# kilo-issue2.net
KiCad netlist of a schematic drawn in EAGLE
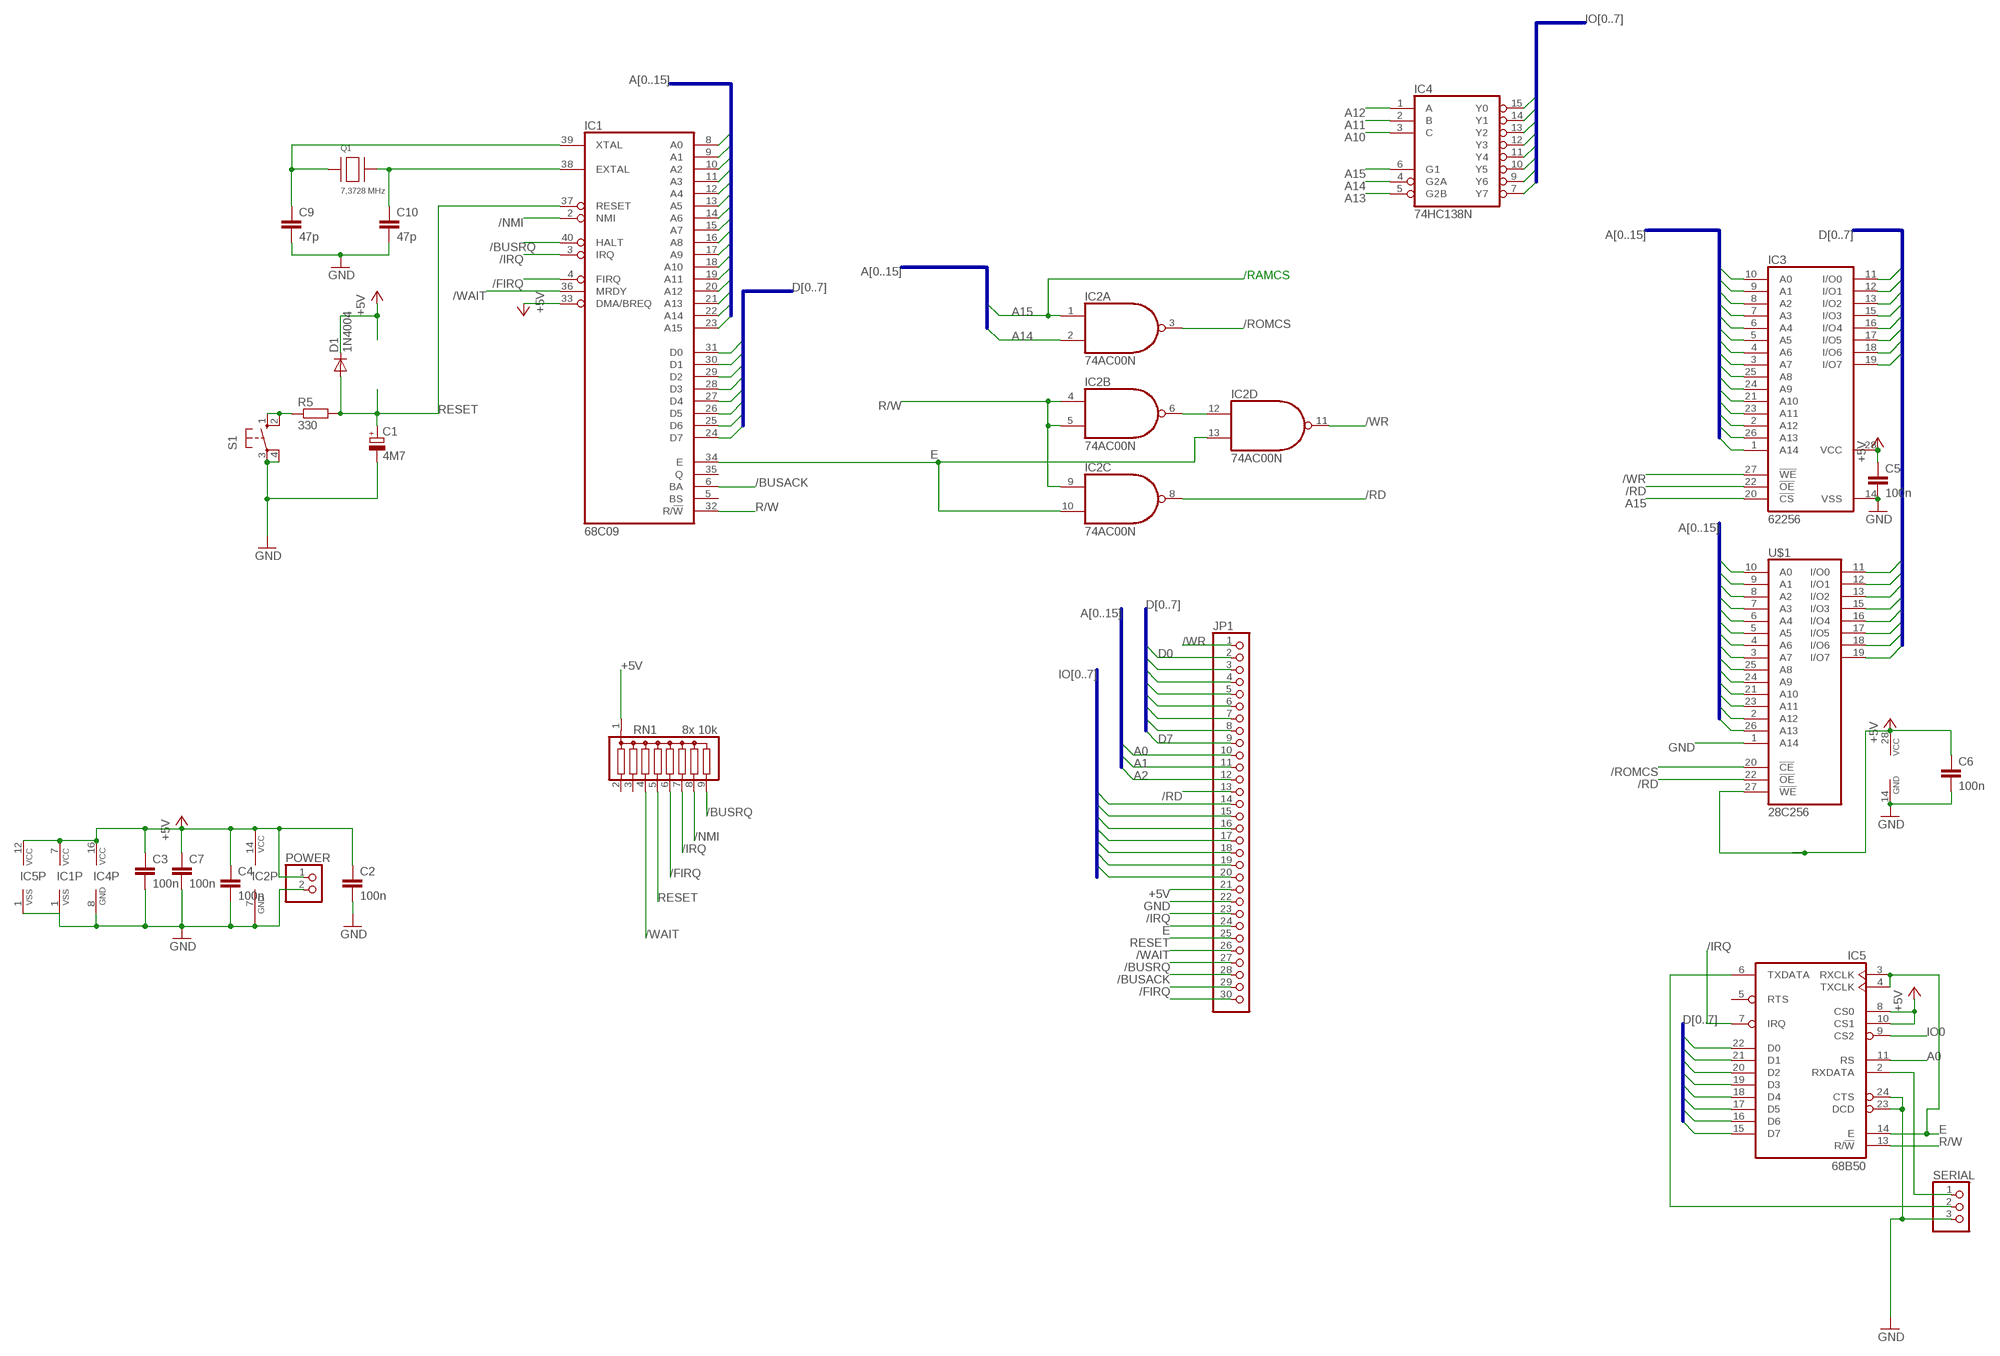
[diagram p0: schematic, sheet 1]

(export (version "E")
  (design (tool "Eeschema 10.0.6"))
  (components
    (comp (ref "C1")
      (value "4M7")
      (footprint "eagle-import:E2,5-6")
      (libsource (lib "eagle-import") (part "CPOL-EUE2.5-6"))
    )
    (comp (ref "C2")
      (value "100n")
      (footprint "eagle-import:C025-030X050")
      (libsource (lib "eagle-import") (part "C-EU025-030X050"))
    )
    (comp (ref "C3")
      (value "100n")
      (footprint "eagle-import:C025-030X050")
      (libsource (lib "eagle-import") (part "C-EU025-030X050"))
    )
    (comp (ref "C4")
      (value "100n")
      (footprint "eagle-import:C025-030X050")
      (libsource (lib "eagle-import") (part "C-EU025-030X050"))
    )
    (comp (ref "C5")
      (value "100n")
      (footprint "eagle-import:C025-030X050")
      (libsource (lib "eagle-import") (part "C-EU025-030X050"))
    )
    (comp (ref "C6")
      (value "100n")
      (footprint "eagle-import:C025-030X050")
      (libsource (lib "eagle-import") (part "C-EU025-030X050"))
    )
    (comp (ref "C7")
      (value "100n")
      (footprint "eagle-import:C025-030X050")
      (libsource (lib "eagle-import") (part "C-EU025-030X050"))
    )
    (comp (ref "C9")
      (value "47p")
      (footprint "eagle-import:C025-030X050")
      (libsource (lib "eagle-import") (part "C-EU025-030X050"))
    )
    (comp (ref "C10")
      (value "47p")
      (footprint "eagle-import:C025-030X050")
      (libsource (lib "eagle-import") (part "C-EU025-030X050"))
    )
    (comp (ref "D1")
      (value "1N4004")
      (footprint "eagle-import:DO41-10")
      (libsource (lib "eagle-import") (part "1N4004"))
    )
    (comp (ref "IC1")
      (value "68C09")
      (footprint "eagle-import:DIL40")
      (fields (field (name "MF") "NTE ELECTRONICS") (field (name "MPN") "NTE6809"))
      (libsource (lib "eagle-import") (part "6809"))
    )
    (comp (ref "IC2")
      (value "74AC00N")
      (footprint "eagle-import:DIL14")
      (libsource (lib "eagle-import") (part "7400NALS"))
    )
    (comp (ref "IC3")
      (value "62256")
      (footprint "eagle-import:DIL28-6")
      (libsource (lib "eagle-import") (part "62256P"))
    )
    (comp (ref "IC4")
      (value "74HC138N")
      (footprint "eagle-import:DIL16")
      (libsource (lib "eagle-import") (part "74138NHC"))
    )
    (comp (ref "IC5")
      (value "68B50")
      (footprint "eagle-import:DIL24")
      (fields (field (name "MF") "NTE ELECTRONICS") (field (name "MPN") "NTE6850"))
      (libsource (lib "eagle-import") (part "6850"))
    )
    (comp (ref "JP1")
      (value "PINHD-1X30")
      (footprint "eagle-import:1X30")
      (libsource (lib "eagle-import") (part "PINHD-1X30"))
    )
    (comp (ref "POWER")
      (value "PINHD-1X2")
      (footprint "eagle-import:1X02")
      (libsource (lib "eagle-import") (part "PINHD-1X2"))
    )
    (comp (ref "Q1")
      (value "7,3728 MHz")
      (footprint "eagle-import:HC49US")
      (libsource (lib "eagle-import") (part "306010080_XTAL_8MHZ_HC49US"))
    )
    (comp (ref "R5")
      (value "330")
      (footprint "eagle-import:0207_7")
      (libsource (lib "eagle-import") (part "R-EU_0207/7"))
    )
    (comp (ref "RN1")
      (value "8x 10k")
      (footprint "eagle-import:SIL9")
      (libsource (lib "eagle-import") (part "G08R"))
    )
    (comp (ref "S1")
      (value "40-XX")
      (footprint "eagle-import:B3F-40XX")
      (fields (field (name "MF") "OMRON COMPONENTS USA") (field (name "MPN") "B3F-4000"))
      (libsource (lib "eagle-import") (part "40-XX"))
    )
    (comp (ref "SERIAL")
      (value "PINHD-1X3")
      (footprint "eagle-import:1X03")
      (libsource (lib "eagle-import") (part "PINHD-1X3"))
    )
    (comp (ref "U$1")
      (value "28C256")
      (footprint "eagle-import:DIL28")
      (libsource (lib "eagle-import") (part "28C256"))
    )
  )
  (nets
    (net (code "1") (name "+5V") (class "Default")
      (node (ref "C2") (pin "1") (pinfunction "1_1") (pintype "passive"))
      (node (ref "C3") (pin "1") (pinfunction "1_1") (pintype "passive"))
      (node (ref "C4") (pin "1") (pinfunction "1_1") (pintype "passive"))
      (node (ref "C5") (pin "1") (pinfunction "1_1") (pintype "passive"))
      (node (ref "C6") (pin "1") (pinfunction "1_1") (pintype "passive"))
      (node (ref "C7") (pin "1") (pinfunction "1_1") (pintype "passive"))
      (node (ref "D1") (pin "C") (pinfunction "C_C") (pintype "passive"))
      (node (ref "IC1") (pin "33") (pinfunction "DMA/BREQ_33") (pintype "input"))
      (node (ref "IC1") (pin "7") (pinfunction "VCC_7") (pintype "power_in"))
      (node (ref "IC2") (pin "14") (pinfunction "VCC_14") (pintype "power_in"))
      (node (ref "IC3") (pin "28") (pinfunction "VCC_28") (pintype "power_in"))
      (node (ref "IC4") (pin "16") (pinfunction "VCC_16") (pintype "power_in"))
      (node (ref "IC5") (pin "10") (pinfunction "CS1_10") (pintype "input"))
      (node (ref "IC5") (pin "12") (pinfunction "VCC_12") (pintype "power_in"))
      (node (ref "IC5") (pin "8") (pinfunction "CS0_8") (pintype "input"))
      (node (ref "JP1") (pin "21") (pinfunction "21_21") (pintype "passive"))
      (node (ref "POWER") (pin "1") (pinfunction "1_1") (pintype "passive"))
      (node (ref "RN1") (pin "1") (pinfunction "1_1") (pintype "passive"))
      (node (ref "U$1") (pin "27") (pinfunction "~{WE}_27") (pintype "input"))
      (node (ref "U$1") (pin "28") (pinfunction "VCC_28") (pintype "power_in"))
    )
    (net (code "5") (name "A0") (class "Default")
      (node (ref "IC1") (pin "8") (pinfunction "A0_8") (pintype "tri_state"))
      (node (ref "IC3") (pin "10") (pinfunction "A0_10") (pintype "input"))
      (node (ref "IC5") (pin "11") (pinfunction "RS_11") (pintype "input"))
      (node (ref "JP1") (pin "10") (pinfunction "10_10") (pintype "passive"))
      (node (ref "U$1") (pin "10") (pinfunction "A0_10") (pintype "input"))
    )
    (net (code "6") (name "A1") (class "Default")
      (node (ref "IC1") (pin "9") (pinfunction "A1_9") (pintype "tri_state"))
      (node (ref "IC3") (pin "9") (pinfunction "A1_9") (pintype "input"))
      (node (ref "JP1") (pin "11") (pinfunction "11_11") (pintype "passive"))
      (node (ref "U$1") (pin "9") (pinfunction "A1_9") (pintype "input"))
    )
    (net (code "7") (name "A2") (class "Default")
      (node (ref "IC1") (pin "10") (pinfunction "A2_10") (pintype "tri_state"))
      (node (ref "IC3") (pin "8") (pinfunction "A2_8") (pintype "input"))
      (node (ref "JP1") (pin "12") (pinfunction "12_12") (pintype "passive"))
      (node (ref "U$1") (pin "8") (pinfunction "A2_8") (pintype "input"))
    )
    (net (code "8") (name "A3") (class "Default")
      (node (ref "IC1") (pin "11") (pinfunction "A3_11") (pintype "tri_state"))
      (node (ref "IC3") (pin "7") (pinfunction "A3_7") (pintype "input"))
      (node (ref "U$1") (pin "7") (pinfunction "A3_7") (pintype "input"))
    )
    (net (code "9") (name "A4") (class "Default")
      (node (ref "IC1") (pin "12") (pinfunction "A4_12") (pintype "tri_state"))
      (node (ref "IC3") (pin "6") (pinfunction "A4_6") (pintype "input"))
      (node (ref "U$1") (pin "6") (pinfunction "A4_6") (pintype "input"))
    )
    (net (code "10") (name "A5") (class "Default")
      (node (ref "IC1") (pin "13") (pinfunction "A5_13") (pintype "tri_state"))
      (node (ref "IC3") (pin "5") (pinfunction "A5_5") (pintype "input"))
      (node (ref "U$1") (pin "5") (pinfunction "A5_5") (pintype "input"))
    )
    (net (code "11") (name "A6") (class "Default")
      (node (ref "IC1") (pin "14") (pinfunction "A6_14") (pintype "tri_state"))
      (node (ref "IC3") (pin "4") (pinfunction "A6_4") (pintype "input"))
      (node (ref "U$1") (pin "4") (pinfunction "A6_4") (pintype "input"))
    )
    (net (code "12") (name "A7") (class "Default")
      (node (ref "IC1") (pin "15") (pinfunction "A7_15") (pintype "tri_state"))
      (node (ref "IC3") (pin "3") (pinfunction "A7_3") (pintype "input"))
      (node (ref "U$1") (pin "3") (pinfunction "A7_3") (pintype "input"))
    )
    (net (code "13") (name "A8") (class "Default")
      (node (ref "IC1") (pin "16") (pinfunction "A8_16") (pintype "tri_state"))
      (node (ref "IC3") (pin "25") (pinfunction "A8_25") (pintype "input"))
      (node (ref "U$1") (pin "25") (pinfunction "A8_25") (pintype "input"))
    )
    (net (code "14") (name "A9") (class "Default")
      (node (ref "IC1") (pin "17") (pinfunction "A9_17") (pintype "tri_state"))
      (node (ref "IC3") (pin "24") (pinfunction "A9_24") (pintype "input"))
      (node (ref "U$1") (pin "24") (pinfunction "A9_24") (pintype "input"))
    )
    (net (code "15") (name "A10") (class "Default")
      (node (ref "IC1") (pin "18") (pinfunction "A10_18") (pintype "tri_state"))
      (node (ref "IC3") (pin "21") (pinfunction "A10_21") (pintype "input"))
      (node (ref "IC4") (pin "3") (pinfunction "C_3") (pintype "input"))
      (node (ref "U$1") (pin "21") (pinfunction "A10_21") (pintype "input"))
    )
    (net (code "16") (name "A11") (class "Default")
      (node (ref "IC1") (pin "19") (pinfunction "A11_19") (pintype "tri_state"))
      (node (ref "IC3") (pin "23") (pinfunction "A11_23") (pintype "input"))
      (node (ref "IC4") (pin "2") (pinfunction "B_2") (pintype "input"))
      (node (ref "U$1") (pin "23") (pinfunction "A11_23") (pintype "input"))
    )
    (net (code "17") (name "A12") (class "Default")
      (node (ref "IC1") (pin "20") (pinfunction "A12_20") (pintype "tri_state"))
      (node (ref "IC3") (pin "2") (pinfunction "A12_2") (pintype "input"))
      (node (ref "IC4") (pin "1") (pinfunction "A_1") (pintype "input"))
      (node (ref "U$1") (pin "2") (pinfunction "A12_2") (pintype "input"))
    )
    (net (code "18") (name "A13") (class "Default")
      (node (ref "IC1") (pin "21") (pinfunction "A13_21") (pintype "tri_state"))
      (node (ref "IC3") (pin "26") (pinfunction "A13_26") (pintype "input"))
      (node (ref "IC4") (pin "5") (pinfunction "G2B_5") (pintype "input"))
      (node (ref "U$1") (pin "26") (pinfunction "A13_26") (pintype "input"))
    )
    (net (code "19") (name "A14") (class "Default")
      (node (ref "IC1") (pin "22") (pinfunction "A14_22") (pintype "tri_state"))
      (node (ref "IC2") (pin "2") (pinfunction "I1_2") (pintype "input"))
      (node (ref "IC3") (pin "1") (pinfunction "A14_1") (pintype "input"))
      (node (ref "IC4") (pin "4") (pinfunction "G2A_4") (pintype "input"))
    )
    (net (code "20") (name "A15") (class "Default")
      (node (ref "IC1") (pin "23") (pinfunction "A15_23") (pintype "tri_state"))
      (node (ref "IC2") (pin "1") (pinfunction "I0_1") (pintype "input"))
      (node (ref "IC3") (pin "20") (pinfunction "~{CS}_20") (pintype "input"))
      (node (ref "IC4") (pin "6") (pinfunction "G1_6") (pintype "input"))
    )
    (net (code "21") (name "D0") (class "Default")
      (node (ref "IC1") (pin "31") (pinfunction "D0_31") (pintype "bidirectional"))
      (node (ref "IC3") (pin "11") (pinfunction "I/O0_11") (pintype "bidirectional"))
      (node (ref "IC5") (pin "22") (pinfunction "D0_22") (pintype "bidirectional"))
      (node (ref "JP1") (pin "2") (pinfunction "2_2") (pintype "passive"))
      (node (ref "U$1") (pin "11") (pinfunction "I/O0_11") (pintype "tri_state"))
    )
    (net (code "22") (name "D1") (class "Default")
      (node (ref "IC1") (pin "30") (pinfunction "D1_30") (pintype "bidirectional"))
      (node (ref "IC3") (pin "12") (pinfunction "I/O1_12") (pintype "bidirectional"))
      (node (ref "IC5") (pin "21") (pinfunction "D1_21") (pintype "bidirectional"))
      (node (ref "JP1") (pin "3") (pinfunction "3_3") (pintype "passive"))
      (node (ref "U$1") (pin "12") (pinfunction "I/O1_12") (pintype "tri_state"))
    )
    (net (code "23") (name "D2") (class "Default")
      (node (ref "IC1") (pin "29") (pinfunction "D2_29") (pintype "bidirectional"))
      (node (ref "IC3") (pin "13") (pinfunction "I/O2_13") (pintype "bidirectional"))
      (node (ref "IC5") (pin "20") (pinfunction "D2_20") (pintype "bidirectional"))
      (node (ref "JP1") (pin "4") (pinfunction "4_4") (pintype "passive"))
      (node (ref "U$1") (pin "13") (pinfunction "I/O2_13") (pintype "tri_state"))
    )
    (net (code "24") (name "D3") (class "Default")
      (node (ref "IC1") (pin "28") (pinfunction "D3_28") (pintype "bidirectional"))
      (node (ref "IC3") (pin "15") (pinfunction "I/O3_15") (pintype "bidirectional"))
      (node (ref "IC5") (pin "19") (pinfunction "D3_19") (pintype "bidirectional"))
      (node (ref "JP1") (pin "5") (pinfunction "5_5") (pintype "passive"))
      (node (ref "U$1") (pin "15") (pinfunction "I/O3_15") (pintype "tri_state"))
    )
    (net (code "25") (name "D4") (class "Default")
      (node (ref "IC1") (pin "27") (pinfunction "D4_27") (pintype "bidirectional"))
      (node (ref "IC3") (pin "16") (pinfunction "I/O4_16") (pintype "bidirectional"))
      (node (ref "IC5") (pin "18") (pinfunction "D4_18") (pintype "bidirectional"))
      (node (ref "JP1") (pin "6") (pinfunction "6_6") (pintype "passive"))
      (node (ref "U$1") (pin "16") (pinfunction "I/O4_16") (pintype "tri_state"))
    )
    (net (code "26") (name "D5") (class "Default")
      (node (ref "IC1") (pin "26") (pinfunction "D5_26") (pintype "bidirectional"))
      (node (ref "IC3") (pin "17") (pinfunction "I/O5_17") (pintype "bidirectional"))
      (node (ref "IC5") (pin "17") (pinfunction "D5_17") (pintype "bidirectional"))
      (node (ref "JP1") (pin "7") (pinfunction "7_7") (pintype "passive"))
      (node (ref "U$1") (pin "17") (pinfunction "I/O5_17") (pintype "tri_state"))
    )
    (net (code "27") (name "D6") (class "Default")
      (node (ref "IC1") (pin "25") (pinfunction "D6_25") (pintype "bidirectional"))
      (node (ref "IC3") (pin "18") (pinfunction "I/O6_18") (pintype "bidirectional"))
      (node (ref "IC5") (pin "16") (pinfunction "D6_16") (pintype "bidirectional"))
      (node (ref "JP1") (pin "8") (pinfunction "8_8") (pintype "passive"))
      (node (ref "U$1") (pin "18") (pinfunction "I/O6_18") (pintype "tri_state"))
    )
    (net (code "28") (name "D7") (class "Default")
      (node (ref "IC1") (pin "24") (pinfunction "D7_24") (pintype "bidirectional"))
      (node (ref "IC3") (pin "19") (pinfunction "I/O7_19") (pintype "bidirectional"))
      (node (ref "IC5") (pin "15") (pinfunction "D7_15") (pintype "bidirectional"))
      (node (ref "JP1") (pin "9") (pinfunction "9_9") (pintype "passive"))
      (node (ref "U$1") (pin "19") (pinfunction "I/O7_19") (pintype "tri_state"))
    )
    (net (code "29") (name "E") (class "Default")
      (node (ref "IC1") (pin "34") (pinfunction "E_34") (pintype "output"))
      (node (ref "IC2") (pin "10") (pinfunction "I1_10") (pintype "input"))
      (node (ref "IC2") (pin "13") (pinfunction "I1_13") (pintype "input"))
      (node (ref "IC5") (pin "14") (pinfunction "E_14") (pintype "input"))
      (node (ref "IC5") (pin "3") (pinfunction "RXCLK_3") (pintype "input"))
      (node (ref "IC5") (pin "4") (pinfunction "TXCLK_4") (pintype "input"))
      (node (ref "JP1") (pin "24") (pinfunction "24_24") (pintype "passive"))
    )
    (net (code "30") (name "GND") (class "Default")
      (node (ref "C1") (pin "-") (pinfunction "-_-") (pintype "passive"))
      (node (ref "C10") (pin "2") (pinfunction "2_2") (pintype "passive"))
      (node (ref "C2") (pin "2") (pinfunction "2_2") (pintype "passive"))
      (node (ref "C3") (pin "2") (pinfunction "2_2") (pintype "passive"))
      (node (ref "C4") (pin "2") (pinfunction "2_2") (pintype "passive"))
      (node (ref "C5") (pin "2") (pinfunction "2_2") (pintype "passive"))
      (node (ref "C6") (pin "2") (pinfunction "2_2") (pintype "passive"))
      (node (ref "C7") (pin "2") (pinfunction "2_2") (pintype "passive"))
      (node (ref "C9") (pin "2") (pinfunction "2_2") (pintype "passive"))
      (node (ref "IC1") (pin "1") (pinfunction "VSS_1") (pintype "power_in"))
      (node (ref "IC2") (pin "7") (pinfunction "GND_7") (pintype "power_in"))
      (node (ref "IC3") (pin "14") (pinfunction "VSS_14") (pintype "power_in"))
      (node (ref "IC4") (pin "8") (pinfunction "GND_8") (pintype "power_in"))
      (node (ref "IC5") (pin "1") (pinfunction "VSS_1") (pintype "power_in"))
      (node (ref "IC5") (pin "23") (pinfunction "DCD_23") (pintype "input"))
      (node (ref "IC5") (pin "24") (pinfunction "CTS_24") (pintype "input"))
      (node (ref "JP1") (pin "22") (pinfunction "22_22") (pintype "passive"))
      (node (ref "POWER") (pin "2") (pinfunction "2_2") (pintype "passive"))
      (node (ref "S1") (pin "3") (pinfunction "P_3") (pintype "passive"))
      (node (ref "S1") (pin "4") (pinfunction "P1_4") (pintype "passive"))
      (node (ref "SERIAL") (pin "3") (pinfunction "3_3") (pintype "passive"))
      (node (ref "U$1") (pin "1") (pinfunction "A14_1") (pintype "input"))
      (node (ref "U$1") (pin "14") (pinfunction "GND_14") (pintype "power_in"))
    )
    (net (code "31") (name "IO0") (class "Default")
      (node (ref "IC4") (pin "15") (pinfunction "Y0_15") (pintype "output"))
      (node (ref "IC5") (pin "9") (pinfunction "CS2_9") (pintype "input"))
    )
    (net (code "32") (name "IO1") (class "Default")
      (node (ref "IC4") (pin "14") (pinfunction "Y1_14") (pintype "output"))
      (node (ref "JP1") (pin "14") (pinfunction "14_14") (pintype "passive"))
    )
    (net (code "33") (name "IO2") (class "Default")
      (node (ref "IC4") (pin "13") (pinfunction "Y2_13") (pintype "output"))
      (node (ref "JP1") (pin "15") (pinfunction "15_15") (pintype "passive"))
    )
    (net (code "34") (name "IO3") (class "Default")
      (node (ref "IC4") (pin "12") (pinfunction "Y3_12") (pintype "output"))
      (node (ref "JP1") (pin "16") (pinfunction "16_16") (pintype "passive"))
    )
    (net (code "35") (name "IO4") (class "Default")
      (node (ref "IC4") (pin "11") (pinfunction "Y4_11") (pintype "output"))
      (node (ref "JP1") (pin "17") (pinfunction "17_17") (pintype "passive"))
    )
    (net (code "36") (name "IO5") (class "Default")
      (node (ref "IC4") (pin "10") (pinfunction "Y5_10") (pintype "output"))
      (node (ref "JP1") (pin "18") (pinfunction "18_18") (pintype "passive"))
    )
    (net (code "37") (name "IO6") (class "Default")
      (node (ref "IC4") (pin "9") (pinfunction "Y6_9") (pintype "output"))
      (node (ref "JP1") (pin "19") (pinfunction "19_19") (pintype "passive"))
    )
    (net (code "38") (name "IO7") (class "Default")
      (node (ref "IC4") (pin "7") (pinfunction "Y7_7") (pintype "output"))
      (node (ref "JP1") (pin "20") (pinfunction "20_20") (pintype "passive"))
    )
    (net (code "39") (name "Net-(IC1A-EXTAL)") (class "Default")
      (node (ref "C10") (pin "1") (pinfunction "1_1") (pintype "passive"))
      (node (ref "IC1") (pin "38") (pinfunction "EXTAL_38") (pintype "input"))
      (node (ref "Q1") (pin "P$2") (pinfunction "P$2_P$2") (pintype "passive"))
    )
    (net (code "40") (name "Net-(IC1A-XTAL)") (class "Default")
      (node (ref "C9") (pin "1") (pinfunction "1_1") (pintype "passive"))
      (node (ref "IC1") (pin "39") (pinfunction "XTAL_39") (pintype "input"))
      (node (ref "Q1") (pin "P$1") (pinfunction "P$1_P$1") (pintype "passive"))
    )
    (net (code "41") (name "Net-(IC2B-O)") (class "Default")
      (node (ref "IC2") (pin "12") (pinfunction "I0_12") (pintype "input"))
      (node (ref "IC2") (pin "6") (pinfunction "O_6") (pintype "output"))
    )
    (net (code "42") (name "Net-(IC5A-RXDATA)") (class "Default")
      (node (ref "IC5") (pin "2") (pinfunction "RXDATA_2") (pintype "input"))
      (node (ref "SERIAL") (pin "1") (pinfunction "1_1") (pintype "passive"))
    )
    (net (code "43") (name "Net-(IC5A-TXDATA)") (class "Default")
      (node (ref "IC5") (pin "6") (pinfunction "TXDATA_6") (pintype "output"))
      (node (ref "SERIAL") (pin "2") (pinfunction "2_2") (pintype "passive"))
    )
    (net (code "44") (name "Net-(S1-S)") (class "Default")
      (node (ref "R5") (pin "1") (pinfunction "1_1") (pintype "passive"))
      (node (ref "S1") (pin "1") (pinfunction "S_1") (pintype "passive"))
      (node (ref "S1") (pin "2") (pinfunction "S1_2") (pintype "passive"))
    )
    (net (code "45") (name "RESET") (class "Default")
      (node (ref "C1") (pin "+") (pinfunction "+_+") (pintype "passive"))
      (node (ref "D1") (pin "A") (pinfunction "A_A") (pintype "passive"))
      (node (ref "IC1") (pin "37") (pinfunction "RESET_37") (pintype "input"))
      (node (ref "JP1") (pin "25") (pinfunction "25_25") (pintype "passive"))
      (node (ref "R5") (pin "2") (pinfunction "2_2") (pintype "passive"))
      (node (ref "RN1") (pin "5") (pinfunction "5_5") (pintype "passive"))
    )
    (net (code "46") (name "R{slash}W") (class "Default")
      (node (ref "IC1") (pin "32") (pinfunction "R/~{W}_32") (pintype "output"))
      (node (ref "IC2") (pin "4") (pinfunction "I0_4") (pintype "input"))
      (node (ref "IC2") (pin "5") (pinfunction "I1_5") (pintype "input"))
      (node (ref "IC2") (pin "9") (pinfunction "I0_9") (pintype "input"))
      (node (ref "IC5") (pin "13") (pinfunction "R/~{W}_13") (pintype "input"))
    )
    (net (code "47") (name "unconnected-(IC1A-BS-Pad5)") (class "Default")
      (node (ref "IC1") (pin "5") (pinfunction "BS_5") (pintype "output"))
    )
    (net (code "48") (name "unconnected-(IC1A-Q-Pad35)") (class "Default")
      (node (ref "IC1") (pin "35") (pinfunction "Q_35") (pintype "output"))
    )
    (net (code "49") (name "unconnected-(IC5A-RTS-Pad5)") (class "Default")
      (node (ref "IC5") (pin "5") (pinfunction "RTS_5") (pintype "output"))
    )
    (net (code "50") (name "unconnected-(JP1-Pad30)") (class "Default")
      (node (ref "JP1") (pin "30") (pinfunction "30_30") (pintype "passive"))
    )
    (net (code "51") (name "unconnected-(RN1-Pad2)") (class "Default")
      (node (ref "RN1") (pin "2") (pinfunction "2_2") (pintype "passive"))
    )
    (net (code "52") (name "unconnected-(RN1-Pad3)") (class "Default")
      (node (ref "RN1") (pin "3") (pinfunction "3_3") (pintype "passive"))
    )
    (net (code "53") (name "{slash}BUSACK") (class "Default")
      (node (ref "IC1") (pin "6") (pinfunction "BA_6") (pintype "output"))
      (node (ref "JP1") (pin "28") (pinfunction "28_28") (pintype "passive"))
    )
    (net (code "54") (name "{slash}BUSRQ") (class "Default")
      (node (ref "IC1") (pin "40") (pinfunction "HALT_40") (pintype "input"))
      (node (ref "JP1") (pin "27") (pinfunction "27_27") (pintype "passive"))
      (node (ref "RN1") (pin "9") (pinfunction "9_9") (pintype "passive"))
    )
    (net (code "55") (name "{slash}FIRQ") (class "Default")
      (node (ref "IC1") (pin "4") (pinfunction "FIRQ_4") (pintype "input"))
      (node (ref "JP1") (pin "29") (pinfunction "29_29") (pintype "passive"))
      (node (ref "RN1") (pin "6") (pinfunction "6_6") (pintype "passive"))
    )
    (net (code "56") (name "{slash}IRQ") (class "Default")
      (node (ref "IC1") (pin "3") (pinfunction "IRQ_3") (pintype "input"))
      (node (ref "IC5") (pin "7") (pinfunction "IRQ_7") (pintype "output"))
      (node (ref "JP1") (pin "23") (pinfunction "23_23") (pintype "passive"))
      (node (ref "RN1") (pin "7") (pinfunction "7_7") (pintype "passive"))
    )
    (net (code "57") (name "{slash}NMI") (class "Default")
      (node (ref "IC1") (pin "2") (pinfunction "NMI_2") (pintype "input"))
      (node (ref "RN1") (pin "8") (pinfunction "8_8") (pintype "passive"))
    )
    (net (code "58") (name "{slash}RD") (class "Default")
      (node (ref "IC2") (pin "8") (pinfunction "O_8") (pintype "output"))
      (node (ref "IC3") (pin "22") (pinfunction "~{OE}_22") (pintype "input"))
      (node (ref "JP1") (pin "13") (pinfunction "13_13") (pintype "passive"))
      (node (ref "U$1") (pin "22") (pinfunction "~{OE}_22") (pintype "input"))
    )
    (net (code "59") (name "{slash}ROMCS") (class "Default")
      (node (ref "IC2") (pin "3") (pinfunction "O_3") (pintype "output"))
      (node (ref "U$1") (pin "20") (pinfunction "~{CE}_20") (pintype "input"))
    )
    (net (code "60") (name "{slash}WAIT") (class "Default")
      (node (ref "IC1") (pin "36") (pinfunction "MRDY_36") (pintype "input"))
      (node (ref "JP1") (pin "26") (pinfunction "26_26") (pintype "passive"))
      (node (ref "RN1") (pin "4") (pinfunction "4_4") (pintype "passive"))
    )
    (net (code "61") (name "{slash}WR") (class "Default")
      (node (ref "IC2") (pin "11") (pinfunction "O_11") (pintype "output"))
      (node (ref "IC3") (pin "27") (pinfunction "~{WE}_27") (pintype "input"))
      (node (ref "JP1") (pin "1") (pinfunction "1_1") (pintype "passive"))
    )
  )
)
